# AT_short_bus.net
KiCad netlist of a schematic drawn in Altium Designer
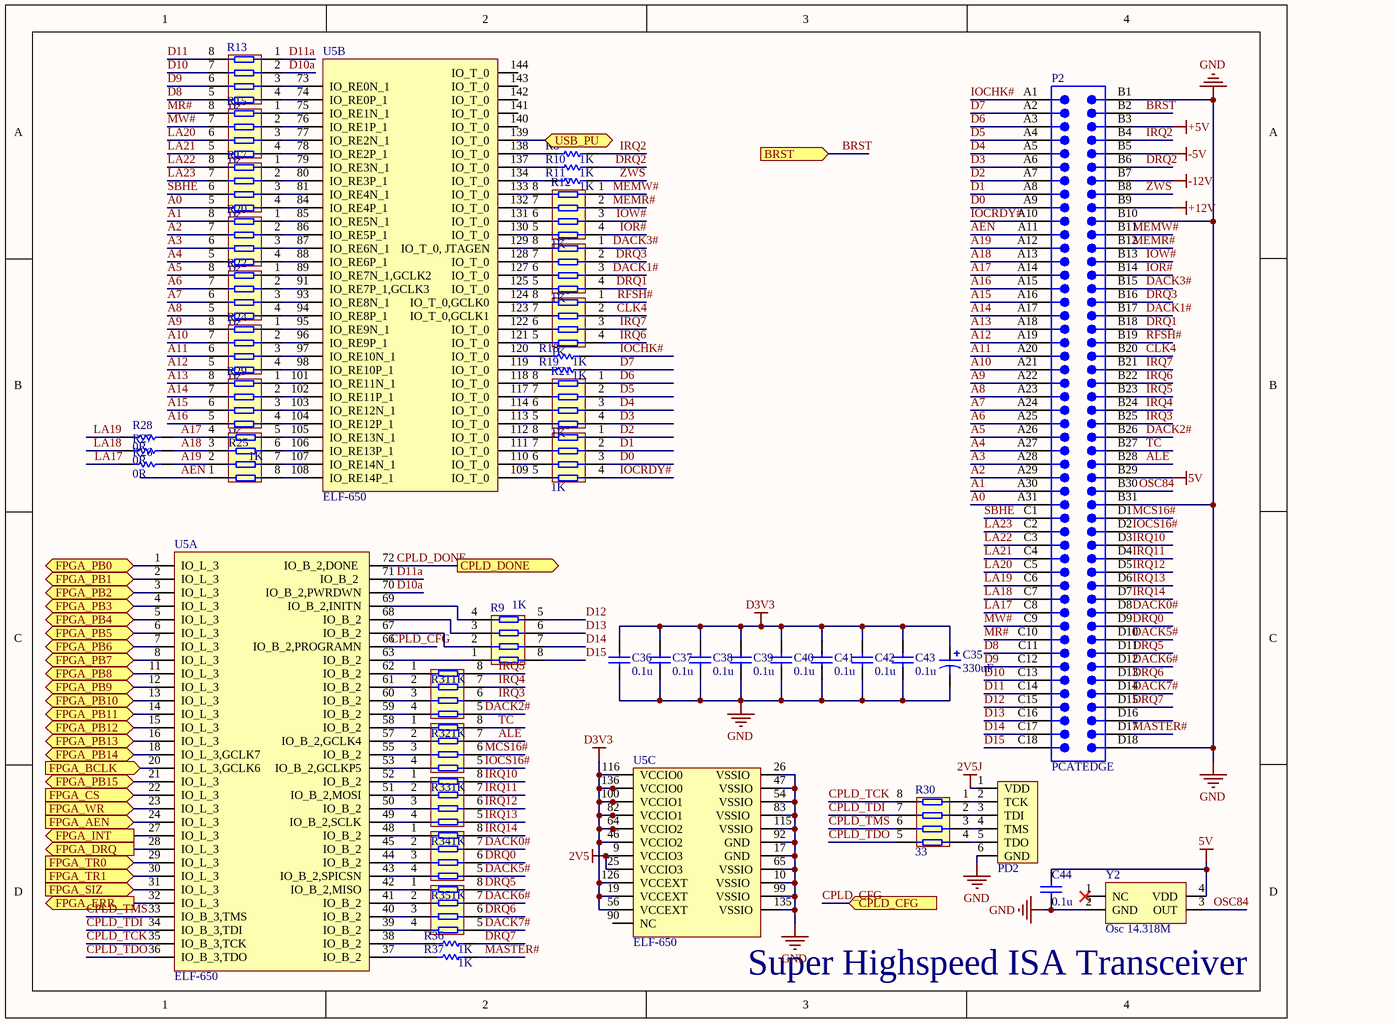
[diagram p0: AT short bus ( 7 x 4.2 inches).schdoc]

(export (version "E")
  (design (tool "Eeschema 10.0.6"))
  (components
    (comp (ref "C35")
      (value "330uF")
      (footprint "TanCap-1210")
      (description "Polarized Capacitor (Radial)")
      (fields (field (name "Comment") "330u") (field (name "PUBLISHER") "Altium Limited"))
      (libsource (lib "Miscellaneous Devices") (part "Cap Pol1"))
    )
    (comp (ref "C36")
      (value "0.1u")
      (footprint "0603C")
      (description "Capacitor")
      (fields (field (name "Comment") "Cap") (field (name "PUBLISHER") "Altium Limited"))
      (libsource (lib "Miscellaneous Devices") (part "Cap"))
    )
    (comp (ref "C37")
      (value "0.1u")
      (footprint "0603C")
      (description "Capacitor")
      (fields (field (name "Comment") "Cap") (field (name "PUBLISHER") "Altium Limited"))
      (libsource (lib "Miscellaneous Devices") (part "Cap"))
    )
    (comp (ref "C38")
      (value "0.1u")
      (footprint "0603C")
      (description "Capacitor")
      (fields (field (name "Comment") "Cap") (field (name "PUBLISHER") "Altium Limited"))
      (libsource (lib "Miscellaneous Devices") (part "Cap"))
    )
    (comp (ref "C39")
      (value "0.1u")
      (footprint "0603C")
      (description "Capacitor")
      (fields (field (name "Comment") "Cap") (field (name "PUBLISHER") "Altium Limited"))
      (libsource (lib "Miscellaneous Devices") (part "Cap"))
    )
    (comp (ref "C40")
      (value "0.1u")
      (footprint "0603C")
      (description "Capacitor")
      (fields (field (name "Comment") "Cap") (field (name "PUBLISHER") "Altium Limited"))
      (libsource (lib "Miscellaneous Devices") (part "Cap"))
    )
    (comp (ref "C41")
      (value "0.1u")
      (footprint "0603C")
      (description "Capacitor")
      (fields (field (name "Comment") "Cap") (field (name "PUBLISHER") "Altium Limited"))
      (libsource (lib "Miscellaneous Devices") (part "Cap"))
    )
    (comp (ref "C42")
      (value "0.1u")
      (footprint "0603C")
      (description "Capacitor")
      (fields (field (name "Comment") "Cap") (field (name "PUBLISHER") "Altium Limited"))
      (libsource (lib "Miscellaneous Devices") (part "Cap"))
    )
    (comp (ref "C43")
      (value "0.1u")
      (footprint "0603C")
      (description "Capacitor")
      (fields (field (name "Comment") "Cap") (field (name "PUBLISHER") "Altium Limited"))
      (libsource (lib "Miscellaneous Devices") (part "Cap"))
    )
    (comp (ref "C44")
      (value "0.1u")
      (footprint "0603C")
      (description "Capacitor")
      (fields (field (name "Comment") "Cap") (field (name "PUBLISHER") "Altium Limited"))
      (libsource (lib "Miscellaneous Devices") (part "Cap"))
    )
    (comp (ref "P2")
      (value "PCATEDGE")
      (footprint "PCATEDGE")
      (description "Card, 98-Position")
      (libsource (lib "*") (part "PCATEDGE"))
    )
    (comp (ref "PD2") (value "JTAG") (footprint "DBGP7") (libsource (lib "RV_AT_Ports") (part "JTAG")))
    (comp (ref "R8")
      (value "1K")
      (footprint "0603R")
      (description "Resistor")
      (fields (field (name "Comment") "Res1") (field (name "PUBLISHER") "Altium Limited"))
      (libsource (lib "Miscellaneous Devices") (part "Res1"))
    )
    (comp (ref "R9") (value "1K") (footprint "YC164") (libsource (lib "") (part "ResPak-8P4R_2")))
    (comp (ref "R10")
      (value "1K")
      (footprint "0603R")
      (description "Resistor")
      (fields (field (name "Comment") "Res1") (field (name "PUBLISHER") "Altium Limited"))
      (libsource (lib "Miscellaneous Devices") (part "Res1"))
    )
    (comp (ref "R11")
      (value "1K")
      (footprint "0603R")
      (description "Resistor")
      (fields (field (name "Comment") "Res1") (field (name "PUBLISHER") "Altium Limited"))
      (libsource (lib "Miscellaneous Devices") (part "Res1"))
    )
    (comp (ref "R12") (value "1K") (footprint "YC164") (libsource (lib "PublicSch") (part "ResPak-8P4R")))
    (comp (ref "R13") (value "1K") (footprint "YC164") (libsource (lib "PublicSch") (part "ResPak-8P4R")))
    (comp (ref "R14") (value "1K") (footprint "YC164") (libsource (lib "PublicSch") (part "ResPak-8P4R")))
    (comp (ref "R15") (value "1K") (footprint "YC164") (libsource (lib "PublicSch") (part "ResPak-8P4R")))
    (comp (ref "R16") (value "1K") (footprint "YC164") (libsource (lib "PublicSch") (part "ResPak-8P4R")))
    (comp (ref "R17") (value "1K") (footprint "YC164") (libsource (lib "PublicSch") (part "ResPak-8P4R")))
    (comp (ref "R18")
      (value "1K")
      (footprint "0603R")
      (description "Resistor")
      (fields (field (name "Comment") "Res1") (field (name "PUBLISHER") "Altium Limited"))
      (libsource (lib "Miscellaneous Devices") (part "Res1"))
    )
    (comp (ref "R19")
      (value "1K")
      (footprint "0603R")
      (description "Resistor")
      (fields (field (name "Comment") "Res1") (field (name "PUBLISHER") "Altium Limited"))
      (libsource (lib "Miscellaneous Devices") (part "Res1"))
    )
    (comp (ref "R20") (value "1K") (footprint "YC164") (libsource (lib "PublicSch") (part "ResPak-8P4R")))
    (comp (ref "R21") (value "1K") (footprint "YC164") (libsource (lib "PublicSch") (part "ResPak-8P4R")))
    (comp (ref "R22") (value "1K") (footprint "YC164") (libsource (lib "PublicSch") (part "ResPak-8P4R")))
    (comp (ref "R23") (value "1K") (footprint "YC164") (libsource (lib "PublicSch") (part "ResPak-8P4R")))
    (comp (ref "R24") (value "1K") (footprint "YC164") (libsource (lib "PublicSch") (part "ResPak-8P4R")))
    (comp (ref "R25") (value "1K") (footprint "YC164") (libsource (lib "") (part "ResPak-8P4R_2")))
    (comp (ref "R26")
      (value "0R")
      (footprint "0603R")
      (description "Resistor")
      (fields (field (name "Comment") "Res1") (field (name "PUBLISHER") "Altium Limited"))
      (libsource (lib "Miscellaneous Devices") (part "Res1"))
    )
    (comp (ref "R27")
      (value "0R")
      (footprint "0603R")
      (description "Resistor")
      (fields (field (name "Comment") "Res1") (field (name "PUBLISHER") "Altium Limited"))
      (libsource (lib "Miscellaneous Devices") (part "Res1"))
    )
    (comp (ref "R28")
      (value "0R")
      (footprint "0603R")
      (description "Resistor")
      (fields (field (name "Comment") "Res1") (field (name "PUBLISHER") "Altium Limited"))
      (libsource (lib "Miscellaneous Devices") (part "Res1"))
    )
    (comp (ref "R29") (value "1K") (footprint "YC164") (libsource (lib "PublicSch") (part "ResPak-8P4R")))
    (comp (ref "R30") (value "33") (footprint "YC164") (libsource (lib "PublicSch") (part "ResPak-8P4R")))
    (comp (ref "R31") (value "1K") (footprint "YC164") (libsource (lib "") (part "ResPak-8P4R_1")))
    (comp (ref "R32") (value "1K") (footprint "YC164") (libsource (lib "") (part "ResPak-8P4R_1")))
    (comp (ref "R33") (value "1K") (footprint "YC164") (libsource (lib "") (part "ResPak-8P4R_1")))
    (comp (ref "R34") (value "1K") (footprint "YC164") (libsource (lib "") (part "ResPak-8P4R_1")))
    (comp (ref "R35") (value "1K") (footprint "YC164") (libsource (lib "") (part "ResPak-8P4R_1")))
    (comp (ref "R36")
      (value "1K")
      (footprint "0603R")
      (description "Resistor")
      (fields (field (name "Comment") "Res1") (field (name "PUBLISHER") "Altium Limited"))
      (libsource (lib "Miscellaneous Devices") (part "Res1"))
    )
    (comp (ref "R37")
      (value "1K")
      (footprint "0603R")
      (description "Resistor")
      (fields (field (name "Comment") "Res1") (field (name "PUBLISHER") "Altium Limited"))
      (libsource (lib "Miscellaneous Devices") (part "Res1"))
    )
    (comp (ref "U5")
      (value "ELF-650")
      (footprint "LQFP144-1")
      (description "GP CPLD")
      (libsource (lib "AnLogic_FPGAs") (part "EF1A650LQ144"))
    )
    (comp (ref "Y2") (value "Osc 14.318M") (footprint "XTAL-3225") (libsource (lib "74xLogic") (part "OSC")))
  )
  (nets
    (net (code "1") (name "+5V") (class "Default")
      (node (ref "P2") (pin "B3") (pinfunction "B3_B3") (pintype "passive"))
    )
    (net (code "2") (name "+12V") (class "Default")
      (node (ref "P2") (pin "B9") (pinfunction "B9_B9") (pintype "passive"))
    )
    (net (code "3") (name "-5V") (class "Default")
      (node (ref "P2") (pin "B5") (pinfunction "B5_B5") (pintype "passive"))
    )
    (net (code "4") (name "-12V") (class "Default")
      (node (ref "P2") (pin "B7") (pinfunction "B7_B7") (pintype "passive"))
    )
    (net (code "5") (name "/A0") (class "Default")
      (node (ref "P2") (pin "A31") (pinfunction "A31_A31") (pintype "passive"))
      (node (ref "R17") (pin "5") (pinfunction "5_5") (pintype "passive"))
    )
    (net (code "6") (name "/A1") (class "Default")
      (node (ref "P2") (pin "A30") (pinfunction "A30_A30") (pintype "passive"))
      (node (ref "R20") (pin "8") (pinfunction "8_8") (pintype "passive"))
    )
    (net (code "7") (name "/A2") (class "Default")
      (node (ref "P2") (pin "A29") (pinfunction "A29_A29") (pintype "passive"))
      (node (ref "R20") (pin "7") (pinfunction "7_7") (pintype "passive"))
    )
    (net (code "8") (name "/A3") (class "Default")
      (node (ref "P2") (pin "A28") (pinfunction "A28_A28") (pintype "passive"))
      (node (ref "R20") (pin "6") (pinfunction "6_6") (pintype "passive"))
    )
    (net (code "9") (name "/A4") (class "Default")
      (node (ref "P2") (pin "A27") (pinfunction "A27_A27") (pintype "passive"))
      (node (ref "R20") (pin "5") (pinfunction "5_5") (pintype "passive"))
    )
    (net (code "10") (name "/A5") (class "Default")
      (node (ref "P2") (pin "A26") (pinfunction "A26_A26") (pintype "passive"))
      (node (ref "R22") (pin "8") (pinfunction "8_8") (pintype "passive"))
    )
    (net (code "11") (name "/A6") (class "Default")
      (node (ref "P2") (pin "A25") (pinfunction "A25_A25") (pintype "passive"))
      (node (ref "R22") (pin "7") (pinfunction "7_7") (pintype "passive"))
    )
    (net (code "12") (name "/A7") (class "Default")
      (node (ref "P2") (pin "A24") (pinfunction "A24_A24") (pintype "passive"))
      (node (ref "R22") (pin "6") (pinfunction "6_6") (pintype "passive"))
    )
    (net (code "13") (name "/A8") (class "Default")
      (node (ref "P2") (pin "A23") (pinfunction "A23_A23") (pintype "passive"))
      (node (ref "R22") (pin "5") (pinfunction "5_5") (pintype "passive"))
    )
    (net (code "14") (name "/A9") (class "Default")
      (node (ref "P2") (pin "A22") (pinfunction "A22_A22") (pintype "passive"))
      (node (ref "R24") (pin "8") (pinfunction "8_8") (pintype "passive"))
    )
    (net (code "15") (name "/A10") (class "Default")
      (node (ref "P2") (pin "A21") (pinfunction "A21_A21") (pintype "passive"))
      (node (ref "R24") (pin "7") (pinfunction "7_7") (pintype "passive"))
    )
    (net (code "16") (name "/A11") (class "Default")
      (node (ref "P2") (pin "A20") (pinfunction "A20_A20") (pintype "passive"))
      (node (ref "R24") (pin "6") (pinfunction "6_6") (pintype "passive"))
    )
    (net (code "17") (name "/A12") (class "Default")
      (node (ref "P2") (pin "A19") (pinfunction "A19_A19") (pintype "passive"))
      (node (ref "R24") (pin "5") (pinfunction "5_5") (pintype "passive"))
    )
    (net (code "18") (name "/A13") (class "Default")
      (node (ref "P2") (pin "A18") (pinfunction "A18_A18") (pintype "passive"))
      (node (ref "R29") (pin "8") (pinfunction "8_8") (pintype "passive"))
    )
    (net (code "19") (name "/A14") (class "Default")
      (node (ref "P2") (pin "A17") (pinfunction "A17_A17") (pintype "passive"))
      (node (ref "R29") (pin "7") (pinfunction "7_7") (pintype "passive"))
    )
    (net (code "20") (name "/A15") (class "Default")
      (node (ref "P2") (pin "A16") (pinfunction "A16_A16") (pintype "passive"))
      (node (ref "R29") (pin "6") (pinfunction "6_6") (pintype "passive"))
    )
    (net (code "21") (name "/A16") (class "Default")
      (node (ref "P2") (pin "A15") (pinfunction "A15_A15") (pintype "passive"))
      (node (ref "R29") (pin "5") (pinfunction "5_5") (pintype "passive"))
    )
    (net (code "22") (name "/A17") (class "Default")
      (node (ref "P2") (pin "A14") (pinfunction "A14_A14") (pintype "passive"))
      (node (ref "R25") (pin "4") (pinfunction "4_4") (pintype "passive"))
      (node (ref "R28") (pin "2") (pinfunction "2_2") (pintype "passive"))
    )
    (net (code "23") (name "/A18") (class "Default")
      (node (ref "P2") (pin "A13") (pinfunction "A13_A13") (pintype "passive"))
      (node (ref "R25") (pin "3") (pinfunction "3_3") (pintype "passive"))
      (node (ref "R27") (pin "2") (pinfunction "2_2") (pintype "passive"))
    )
    (net (code "24") (name "/A19") (class "Default")
      (node (ref "P2") (pin "A12") (pinfunction "A12_A12") (pintype "passive"))
      (node (ref "R25") (pin "2") (pinfunction "2_2") (pintype "passive"))
      (node (ref "R26") (pin "2") (pinfunction "2_2") (pintype "passive"))
    )
    (net (code "25") (name "/AEN") (class "Default")
      (node (ref "P2") (pin "A11") (pinfunction "A11_A11") (pintype "passive"))
      (node (ref "R25") (pin "1") (pinfunction "1_1") (pintype "passive"))
    )
    (net (code "26") (name "/ALE") (class "Default")
      (node (ref "P2") (pin "B28") (pinfunction "B28_B28") (pintype "passive"))
      (node (ref "R32") (pin "7") (pinfunction "7_7") (pintype "passive"))
    )
    (net (code "27") (name "/BRST") (class "Default")
      (node (ref "P2") (pin "B2") (pinfunction "B2_B2") (pintype "passive"))
    )
    (net (code "28") (name "/CLK4") (class "Default")
      (node (ref "P2") (pin "B20") (pinfunction "B20_B20") (pintype "passive"))
      (node (ref "R16") (pin "2") (pinfunction "2_2") (pintype "passive"))
    )
    (net (code "29") (name "/CPLD_CFG") (class "Default")
      (node (ref "U5") (pin "66") (pinfunction "IO_B_2,PROGRAMN_66") (pintype "passive"))
    )
    (net (code "30") (name "/CPLD_DONE") (class "Default")
      (node (ref "U5") (pin "72") (pinfunction "IO_B_2,DONE_72") (pintype "passive"))
    )
    (net (code "31") (name "/CPLD_TCK") (class "Default")
      (node (ref "R30") (pin "8") (pinfunction "8_8") (pintype "passive"))
      (node (ref "U5") (pin "35") (pinfunction "IO_B_3,TCK_35") (pintype "passive"))
    )
    (net (code "32") (name "/CPLD_TDI") (class "Default")
      (node (ref "R30") (pin "7") (pinfunction "7_7") (pintype "passive"))
      (node (ref "U5") (pin "34") (pinfunction "IO_B_3,TDI_34") (pintype "passive"))
    )
    (net (code "33") (name "/CPLD_TDO") (class "Default")
      (node (ref "R30") (pin "5") (pinfunction "5_5") (pintype "passive"))
      (node (ref "U5") (pin "36") (pinfunction "IO_B_3,TDO_36") (pintype "passive"))
    )
    (net (code "34") (name "/CPLD_TMS") (class "Default")
      (node (ref "R30") (pin "6") (pinfunction "6_6") (pintype "passive"))
      (node (ref "U5") (pin "33") (pinfunction "IO_B_3,TMS_33") (pintype "passive"))
    )
    (net (code "35") (name "/D0") (class "Default")
      (node (ref "P2") (pin "A9") (pinfunction "A9_A9") (pintype "passive"))
      (node (ref "R23") (pin "3") (pinfunction "3_3") (pintype "passive"))
    )
    (net (code "36") (name "/D1") (class "Default")
      (node (ref "P2") (pin "A8") (pinfunction "A8_A8") (pintype "passive"))
      (node (ref "R23") (pin "2") (pinfunction "2_2") (pintype "passive"))
    )
    (net (code "37") (name "/D2") (class "Default")
      (node (ref "P2") (pin "A7") (pinfunction "A7_A7") (pintype "passive"))
      (node (ref "R23") (pin "1") (pinfunction "1_1") (pintype "passive"))
    )
    (net (code "38") (name "/D3") (class "Default")
      (node (ref "P2") (pin "A6") (pinfunction "A6_A6") (pintype "passive"))
      (node (ref "R21") (pin "4") (pinfunction "4_4") (pintype "passive"))
    )
    (net (code "39") (name "/D4") (class "Default")
      (node (ref "P2") (pin "A5") (pinfunction "A5_A5") (pintype "passive"))
      (node (ref "R21") (pin "3") (pinfunction "3_3") (pintype "passive"))
    )
    (net (code "40") (name "/D5") (class "Default")
      (node (ref "P2") (pin "A4") (pinfunction "A4_A4") (pintype "passive"))
      (node (ref "R21") (pin "2") (pinfunction "2_2") (pintype "passive"))
    )
    (net (code "41") (name "/D6") (class "Default")
      (node (ref "P2") (pin "A3") (pinfunction "A3_A3") (pintype "passive"))
      (node (ref "R21") (pin "1") (pinfunction "1_1") (pintype "passive"))
    )
    (net (code "42") (name "/D7") (class "Default")
      (node (ref "P2") (pin "A2") (pinfunction "A2_A2") (pintype "passive"))
      (node (ref "R19") (pin "1") (pinfunction "1_1") (pintype "passive"))
    )
    (net (code "43") (name "/D8") (class "Default")
      (node (ref "P2") (pin "C11") (pinfunction "C11_C11") (pintype "passive"))
      (node (ref "R13") (pin "5") (pinfunction "5_5") (pintype "passive"))
    )
    (net (code "44") (name "/D9") (class "Default")
      (node (ref "P2") (pin "C12") (pinfunction "C12_C12") (pintype "passive"))
      (node (ref "R13") (pin "6") (pinfunction "6_6") (pintype "passive"))
    )
    (net (code "45") (name "/D10") (class "Default")
      (node (ref "P2") (pin "C13") (pinfunction "C13_C13") (pintype "passive"))
      (node (ref "R13") (pin "7") (pinfunction "7_7") (pintype "passive"))
    )
    (net (code "46") (name "/D10a") (class "Default")
      (node (ref "R13") (pin "2") (pinfunction "2_2") (pintype "passive"))
      (node (ref "U5") (pin "70") (pinfunction "IO_B_2,PWRDWN_70") (pintype "passive"))
    )
    (net (code "47") (name "/D11") (class "Default")
      (node (ref "P2") (pin "C14") (pinfunction "C14_C14") (pintype "passive"))
      (node (ref "R13") (pin "8") (pinfunction "8_8") (pintype "passive"))
    )
    (net (code "48") (name "/D11a") (class "Default")
      (node (ref "R13") (pin "1") (pinfunction "1_1") (pintype "passive"))
      (node (ref "U5") (pin "71") (pinfunction "IO_B_2_71") (pintype "passive"))
    )
    (net (code "49") (name "/D12") (class "Default")
      (node (ref "P2") (pin "C15") (pinfunction "C15_C15") (pintype "passive"))
      (node (ref "R9") (pin "5") (pinfunction "5_5") (pintype "passive"))
    )
    (net (code "50") (name "/D13") (class "Default")
      (node (ref "P2") (pin "C16") (pinfunction "C16_C16") (pintype "passive"))
      (node (ref "R9") (pin "6") (pinfunction "6_6") (pintype "passive"))
    )
    (net (code "51") (name "/D14") (class "Default")
      (node (ref "P2") (pin "C17") (pinfunction "C17_C17") (pintype "passive"))
      (node (ref "R9") (pin "7") (pinfunction "7_7") (pintype "passive"))
    )
    (net (code "52") (name "/D15") (class "Default")
      (node (ref "P2") (pin "C18") (pinfunction "C18_C18") (pintype "passive"))
      (node (ref "R9") (pin "8") (pinfunction "8_8") (pintype "passive"))
    )
    (net (code "53") (name "/DACK0#") (class "Default")
      (node (ref "P2") (pin "D8") (pinfunction "D8_D8") (pintype "passive"))
      (node (ref "R34") (pin "7") (pinfunction "7_7") (pintype "passive"))
    )
    (net (code "54") (name "/DACK1#") (class "Default")
      (node (ref "P2") (pin "B17") (pinfunction "B17_B17") (pintype "passive"))
      (node (ref "R14") (pin "3") (pinfunction "3_3") (pintype "passive"))
    )
    (net (code "55") (name "/DACK2#") (class "Default")
      (node (ref "P2") (pin "B26") (pinfunction "B26_B26") (pintype "passive"))
      (node (ref "R31") (pin "5") (pinfunction "5_5") (pintype "passive"))
    )
    (net (code "56") (name "/DACK3#") (class "Default")
      (node (ref "P2") (pin "B15") (pinfunction "B15_B15") (pintype "passive"))
      (node (ref "R14") (pin "1") (pinfunction "1_1") (pintype "passive"))
    )
    (net (code "57") (name "/DACK5#") (class "Default")
      (node (ref "P2") (pin "D10") (pinfunction "D10_D10") (pintype "passive"))
      (node (ref "R34") (pin "5") (pinfunction "5_5") (pintype "passive"))
    )
    (net (code "58") (name "/DACK6#") (class "Default")
      (node (ref "P2") (pin "D12") (pinfunction "D12_D12") (pintype "passive"))
      (node (ref "R35") (pin "7") (pinfunction "7_7") (pintype "passive"))
    )
    (net (code "59") (name "/DACK7#") (class "Default")
      (node (ref "P2") (pin "D14") (pinfunction "D14_D14") (pintype "passive"))
      (node (ref "R35") (pin "5") (pinfunction "5_5") (pintype "passive"))
    )
    (net (code "60") (name "/DRQ0") (class "Default")
      (node (ref "P2") (pin "D9") (pinfunction "D9_D9") (pintype "passive"))
      (node (ref "R34") (pin "6") (pinfunction "6_6") (pintype "passive"))
    )
    (net (code "61") (name "/DRQ1") (class "Default")
      (node (ref "P2") (pin "B18") (pinfunction "B18_B18") (pintype "passive"))
      (node (ref "R14") (pin "4") (pinfunction "4_4") (pintype "passive"))
    )
    (net (code "62") (name "/DRQ2") (class "Default")
      (node (ref "P2") (pin "B6") (pinfunction "B6_B6") (pintype "passive"))
      (node (ref "R10") (pin "1") (pinfunction "1_1") (pintype "passive"))
    )
    (net (code "63") (name "/DRQ3") (class "Default")
      (node (ref "P2") (pin "B16") (pinfunction "B16_B16") (pintype "passive"))
      (node (ref "R14") (pin "2") (pinfunction "2_2") (pintype "passive"))
    )
    (net (code "64") (name "/DRQ5") (class "Default")
      (node (ref "P2") (pin "D11") (pinfunction "D11_D11") (pintype "passive"))
      (node (ref "R35") (pin "8") (pinfunction "8_8") (pintype "passive"))
    )
    (net (code "65") (name "/DRQ6") (class "Default")
      (node (ref "P2") (pin "D13") (pinfunction "D13_D13") (pintype "passive"))
      (node (ref "R35") (pin "6") (pinfunction "6_6") (pintype "passive"))
    )
    (net (code "66") (name "/DRQ7") (class "Default")
      (node (ref "P2") (pin "D15") (pinfunction "D15_D15") (pintype "passive"))
      (node (ref "R36") (pin "1") (pinfunction "1_1") (pintype "passive"))
    )
    (net (code "67") (name "/FPGA_AEN") (class "Default")
      (node (ref "U5") (pin "24") (pinfunction "IO_L_3_24") (pintype "passive"))
    )
    (net (code "68") (name "/FPGA_BCLK") (class "Default")
      (node (ref "U5") (pin "20") (pinfunction "IO_L_3,GCLK6_20") (pintype "passive"))
    )
    (net (code "69") (name "/FPGA_CS") (class "Default")
      (node (ref "U5") (pin "22") (pinfunction "IO_L_3_22") (pintype "passive"))
    )
    (net (code "70") (name "/FPGA_DRQ") (class "Default")
      (node (ref "U5") (pin "28") (pinfunction "IO_L_3_28") (pintype "passive"))
    )
    (net (code "71") (name "/FPGA_ERR") (class "Default")
      (node (ref "U5") (pin "32") (pinfunction "IO_L_3_32") (pintype "passive"))
    )
    (net (code "72") (name "/FPGA_INT") (class "Default")
      (node (ref "U5") (pin "27") (pinfunction "IO_L_3_27") (pintype "passive"))
    )
    (net (code "73") (name "/FPGA_PB0") (class "Default")
      (node (ref "U5") (pin "1") (pinfunction "IO_L_3_1") (pintype "passive"))
    )
    (net (code "74") (name "/FPGA_PB1") (class "Default")
      (node (ref "U5") (pin "2") (pinfunction "IO_L_3_2") (pintype "passive"))
    )
    (net (code "75") (name "/FPGA_PB2") (class "Default")
      (node (ref "U5") (pin "3") (pinfunction "IO_L_3_3") (pintype "passive"))
    )
    (net (code "76") (name "/FPGA_PB3") (class "Default")
      (node (ref "U5") (pin "4") (pinfunction "IO_L_3_4") (pintype "passive"))
    )
    (net (code "77") (name "/FPGA_PB4") (class "Default")
      (node (ref "U5") (pin "5") (pinfunction "IO_L_3_5") (pintype "passive"))
    )
    (net (code "78") (name "/FPGA_PB5") (class "Default")
      (node (ref "U5") (pin "6") (pinfunction "IO_L_3_6") (pintype "passive"))
    )
    (net (code "79") (name "/FPGA_PB6") (class "Default")
      (node (ref "U5") (pin "7") (pinfunction "IO_L_3_7") (pintype "passive"))
    )
    (net (code "80") (name "/FPGA_PB7") (class "Default")
      (node (ref "U5") (pin "8") (pinfunction "IO_L_3_8") (pintype "passive"))
    )
    (net (code "81") (name "/FPGA_PB8") (class "Default")
      (node (ref "U5") (pin "11") (pinfunction "IO_L_3_11") (pintype "passive"))
    )
    (net (code "82") (name "/FPGA_PB9") (class "Default")
      (node (ref "U5") (pin "12") (pinfunction "IO_L_3_12") (pintype "passive"))
    )
    (net (code "83") (name "/FPGA_PB10") (class "Default")
      (node (ref "U5") (pin "13") (pinfunction "IO_L_3_13") (pintype "passive"))
    )
    (net (code "84") (name "/FPGA_PB11") (class "Default")
      (node (ref "U5") (pin "14") (pinfunction "IO_L_3_14") (pintype "passive"))
    )
    (net (code "85") (name "/FPGA_PB12") (class "Default")
      (node (ref "U5") (pin "15") (pinfunction "IO_L_3_15") (pintype "passive"))
    )
    (net (code "86") (name "/FPGA_PB13") (class "Default")
      (node (ref "U5") (pin "16") (pinfunction "IO_L_3_16") (pintype "passive"))
    )
    (net (code "87") (name "/FPGA_PB14") (class "Default")
      (node (ref "U5") (pin "18") (pinfunction "IO_L_3,GCLK7_18") (pintype "passive"))
    )
    (net (code "88") (name "/FPGA_PB15") (class "Default")
      (node (ref "U5") (pin "21") (pinfunction "IO_L_3_21") (pintype "passive"))
    )
    (net (code "89") (name "/FPGA_SIZ") (class "Default")
      (node (ref "U5") (pin "31") (pinfunction "IO_L_3_31") (pintype "passive"))
    )
    (net (code "90") (name "/FPGA_TR0") (class "Default")
      (node (ref "U5") (pin "29") (pinfunction "IO_L_3_29") (pintype "passive"))
    )
    (net (code "91") (name "/FPGA_TR1") (class "Default")
      (node (ref "U5") (pin "30") (pinfunction "IO_L_3_30") (pintype "passive"))
    )
    (net (code "92") (name "/FPGA_WR") (class "Default")
      (node (ref "U5") (pin "23") (pinfunction "IO_L_3_23") (pintype "passive"))
    )
    (net (code "93") (name "/IOCHK#") (class "Default")
      (node (ref "P2") (pin "A1") (pinfunction "A1_A1") (pintype "passive"))
      (node (ref "R18") (pin "1") (pinfunction "1_1") (pintype "passive"))
    )
    (net (code "94") (name "/IOCRDY#") (class "Default")
      (node (ref "P2") (pin "A10") (pinfunction "A10_A10") (pintype "passive"))
      (node (ref "R23") (pin "4") (pinfunction "4_4") (pintype "passive"))
    )
    (net (code "95") (name "/IOCS16#") (class "Default")
      (node (ref "P2") (pin "D2") (pinfunction "D2_D2") (pintype "passive"))
      (node (ref "R32") (pin "5") (pinfunction "5_5") (pintype "passive"))
    )
    (net (code "96") (name "/IOR#") (class "Default")
      (node (ref "P2") (pin "B14") (pinfunction "B14_B14") (pintype "passive"))
      (node (ref "R12") (pin "4") (pinfunction "4_4") (pintype "passive"))
    )
    (net (code "97") (name "/IOW#") (class "Default")
      (node (ref "P2") (pin "B13") (pinfunction "B13_B13") (pintype "passive"))
      (node (ref "R12") (pin "3") (pinfunction "3_3") (pintype "passive"))
    )
    (net (code "98") (name "/IRQ2") (class "Default")
      (node (ref "P2") (pin "B4") (pinfunction "B4_B4") (pintype "passive"))
      (node (ref "R8") (pin "1") (pinfunction "1_1") (pintype "passive"))
    )
    (net (code "99") (name "/IRQ3") (class "Default")
      (node (ref "P2") (pin "B25") (pinfunction "B25_B25") (pintype "passive"))
      (node (ref "R31") (pin "6") (pinfunction "6_6") (pintype "passive"))
    )
    (net (code "100") (name "/IRQ4") (class "Default")
      (node (ref "P2") (pin "B24") (pinfunction "B24_B24") (pintype "passive"))
      (node (ref "R31") (pin "7") (pinfunction "7_7") (pintype "passive"))
    )
    (net (code "101") (name "/IRQ5") (class "Default")
      (node (ref "P2") (pin "B23") (pinfunction "B23_B23") (pintype "passive"))
      (node (ref "R31") (pin "8") (pinfunction "8_8") (pintype "passive"))
    )
    (net (code "102") (name "/IRQ6") (class "Default")
      (node (ref "P2") (pin "B22") (pinfunction "B22_B22") (pintype "passive"))
      (node (ref "R16") (pin "4") (pinfunction "4_4") (pintype "passive"))
    )
    (net (code "103") (name "/IRQ7") (class "Default")
      (node (ref "P2") (pin "B21") (pinfunction "B21_B21") (pintype "passive"))
      (node (ref "R16") (pin "3") (pinfunction "3_3") (pintype "passive"))
    )
    (net (code "104") (name "/IRQ10") (class "Default")
      (node (ref "P2") (pin "D3") (pinfunction "D3_D3") (pintype "passive"))
      (node (ref "R33") (pin "8") (pinfunction "8_8") (pintype "passive"))
    )
    (net (code "105") (name "/IRQ11") (class "Default")
      (node (ref "P2") (pin "D4") (pinfunction "D4_D4") (pintype "passive"))
      (node (ref "R33") (pin "7") (pinfunction "7_7") (pintype "passive"))
    )
    (net (code "106") (name "/IRQ12") (class "Default")
      (node (ref "P2") (pin "D5") (pinfunction "D5_D5") (pintype "passive"))
      (node (ref "R33") (pin "6") (pinfunction "6_6") (pintype "passive"))
    )
    (net (code "107") (name "/IRQ13") (class "Default")
      (node (ref "P2") (pin "D6") (pinfunction "D6_D6") (pintype "passive"))
      (node (ref "R33") (pin "5") (pinfunction "5_5") (pintype "passive"))
    )
    (net (code "108") (name "/IRQ14") (class "Default")
      (node (ref "P2") (pin "D7") (pinfunction "D7_D7") (pintype "passive"))
      (node (ref "R34") (pin "8") (pinfunction "8_8") (pintype "passive"))
    )
    (net (code "109") (name "/LA17") (class "Default")
      (node (ref "P2") (pin "C8") (pinfunction "C8_C8") (pintype "passive"))
      (node (ref "R26") (pin "1") (pinfunction "1_1") (pintype "passive"))
    )
    (net (code "110") (name "/LA18") (class "Default")
      (node (ref "P2") (pin "C7") (pinfunction "C7_C7") (pintype "passive"))
      (node (ref "R27") (pin "1") (pinfunction "1_1") (pintype "passive"))
    )
    (net (code "111") (name "/LA19") (class "Default")
      (node (ref "P2") (pin "C6") (pinfunction "C6_C6") (pintype "passive"))
      (node (ref "R28") (pin "1") (pinfunction "1_1") (pintype "passive"))
    )
    (net (code "112") (name "/LA20") (class "Default")
      (node (ref "P2") (pin "C5") (pinfunction "C5_C5") (pintype "passive"))
      (node (ref "R15") (pin "6") (pinfunction "6_6") (pintype "passive"))
    )
    (net (code "113") (name "/LA21") (class "Default")
      (node (ref "P2") (pin "C4") (pinfunction "C4_C4") (pintype "passive"))
      (node (ref "R15") (pin "5") (pinfunction "5_5") (pintype "passive"))
    )
    (net (code "114") (name "/LA22") (class "Default")
      (node (ref "P2") (pin "C3") (pinfunction "C3_C3") (pintype "passive"))
      (node (ref "R17") (pin "8") (pinfunction "8_8") (pintype "passive"))
    )
    (net (code "115") (name "/LA23") (class "Default")
      (node (ref "P2") (pin "C2") (pinfunction "C2_C2") (pintype "passive"))
      (node (ref "R17") (pin "7") (pinfunction "7_7") (pintype "passive"))
    )
    (net (code "116") (name "/MASTER#") (class "Default")
      (node (ref "P2") (pin "D17") (pinfunction "D17_D17") (pintype "passive"))
      (node (ref "R37") (pin "1") (pinfunction "1_1") (pintype "passive"))
    )
    (net (code "117") (name "/MCS16#") (class "Default")
      (node (ref "P2") (pin "D1") (pinfunction "D1_D1") (pintype "passive"))
      (node (ref "R32") (pin "6") (pinfunction "6_6") (pintype "passive"))
    )
    (net (code "118") (name "/MEMR#") (class "Default")
      (node (ref "P2") (pin "B12") (pinfunction "B12_B12") (pintype "passive"))
      (node (ref "R12") (pin "2") (pinfunction "2_2") (pintype "passive"))
    )
    (net (code "119") (name "/MEMW#") (class "Default")
      (node (ref "P2") (pin "B11") (pinfunction "B11_B11") (pintype "passive"))
      (node (ref "R12") (pin "1") (pinfunction "1_1") (pintype "passive"))
    )
    (net (code "120") (name "/MR#") (class "Default")
      (node (ref "P2") (pin "C10") (pinfunction "C10_C10") (pintype "passive"))
      (node (ref "R15") (pin "8") (pinfunction "8_8") (pintype "passive"))
    )
    (net (code "121") (name "/MW#") (class "Default")
      (node (ref "P2") (pin "C9") (pinfunction "C9_C9") (pintype "passive"))
      (node (ref "R15") (pin "7") (pinfunction "7_7") (pintype "passive"))
    )
    (net (code "122") (name "/OSC84") (class "Default")
      (node (ref "P2") (pin "B30") (pinfunction "B30_B30") (pintype "passive"))
      (node (ref "Y2") (pin "3") (pinfunction "OUT_3") (pintype "passive"))
    )
    (net (code "123") (name "/RFSH#") (class "Default")
      (node (ref "P2") (pin "B19") (pinfunction "B19_B19") (pintype "passive"))
      (node (ref "R16") (pin "1") (pinfunction "1_1") (pintype "passive"))
    )
    (net (code "124") (name "/SBHE") (class "Default")
      (node (ref "P2") (pin "C1") (pinfunction "C1_C1") (pintype "passive"))
      (node (ref "R17") (pin "6") (pinfunction "6_6") (pintype "passive"))
    )
    (net (code "125") (name "/TC") (class "Default")
      (node (ref "P2") (pin "B27") (pinfunction "B27_B27") (pintype "passive"))
      (node (ref "R32") (pin "8") (pinfunction "8_8") (pintype "passive"))
    )
    (net (code "126") (name "/USB_PU") (class "Default")
      (node (ref "U5") (pin "139") (pinfunction "IO_T_0_139") (pintype "passive"))
    )
    (net (code "127") (name "/ZWS") (class "Default")
      (node (ref "P2") (pin "B8") (pinfunction "B8_B8") (pintype "passive"))
      (node (ref "R11") (pin "1") (pinfunction "1_1") (pintype "passive"))
    )
    (net (code "128") (name "2V5") (class "Default")
      (node (ref "U5") (pin "25") (pinfunction "VCCIO3_25") (pintype "passive"))
      (node (ref "U5") (pin "9") (pinfunction "VCCIO3_9") (pintype "passive"))
    )
    (net (code "129") (name "2V5J") (class "Default")
      (node (ref "PD2") (pin "1") (pinfunction "VDD_1") (pintype "passive"))
    )
    (net (code "130") (name "5V") (class "Default")
      (node (ref "C44") (pin "2") (pinfunction "2_2") (pintype "passive"))
      (node (ref "P2") (pin "B29") (pinfunction "B29_B29") (pintype "passive"))
      (node (ref "Y2") (pin "4") (pinfunction "VDD_4") (pintype "passive"))
    )
    (net (code "131") (name "D3V3") (class "Default")
      (node (ref "C35") (pin "1") (pinfunction "1_1") (pintype "passive"))
      (node (ref "C36") (pin "1") (pinfunction "1_1") (pintype "passive"))
      (node (ref "C37") (pin "1") (pinfunction "1_1") (pintype "passive"))
      (node (ref "C38") (pin "1") (pinfunction "1_1") (pintype "passive"))
      (node (ref "C39") (pin "1") (pinfunction "1_1") (pintype "passive"))
      (node (ref "C40") (pin "1") (pinfunction "1_1") (pintype "passive"))
      (node (ref "C41") (pin "1") (pinfunction "1_1") (pintype "passive"))
      (node (ref "C42") (pin "1") (pinfunction "1_1") (pintype "passive"))
      (node (ref "C43") (pin "1") (pinfunction "1_1") (pintype "passive"))
      (node (ref "U5") (pin "100") (pinfunction "VCCIO1_100") (pintype "passive"))
      (node (ref "U5") (pin "116") (pinfunction "VCCIO0_116") (pintype "passive"))
      (node (ref "U5") (pin "126") (pinfunction "VCCEXT_126") (pintype "passive"))
      (node (ref "U5") (pin "136") (pinfunction "VCCIO0_136") (pintype "passive"))
      (node (ref "U5") (pin "19") (pinfunction "VCCEXT_19") (pintype "passive"))
      (node (ref "U5") (pin "46") (pinfunction "VCCIO2_46") (pintype "passive"))
      (node (ref "U5") (pin "56") (pinfunction "VCCEXT_56") (pintype "passive"))
      (node (ref "U5") (pin "64") (pinfunction "VCCIO2_64") (pintype "passive"))
      (node (ref "U5") (pin "82") (pinfunction "VCCIO1_82") (pintype "passive"))
    )
    (net (code "132") (name "GND") (class "Default")
      (node (ref "C35") (pin "2") (pinfunction "2_2") (pintype "passive"))
      (node (ref "C36") (pin "2") (pinfunction "2_2") (pintype "passive"))
      (node (ref "C37") (pin "2") (pinfunction "2_2") (pintype "passive"))
      (node (ref "C38") (pin "2") (pinfunction "2_2") (pintype "passive"))
      (node (ref "C39") (pin "2") (pinfunction "2_2") (pintype "passive"))
      (node (ref "C40") (pin "2") (pinfunction "2_2") (pintype "passive"))
      (node (ref "C41") (pin "2") (pinfunction "2_2") (pintype "passive"))
      (node (ref "C42") (pin "2") (pinfunction "2_2") (pintype "passive"))
      (node (ref "C43") (pin "2") (pinfunction "2_2") (pintype "passive"))
      (node (ref "C44") (pin "1") (pinfunction "1_1") (pintype "passive"))
      (node (ref "P2") (pin "B1") (pinfunction "B1_B1") (pintype "passive"))
      (node (ref "P2") (pin "B10") (pinfunction "B10_B10") (pintype "passive"))
      (node (ref "P2") (pin "B31") (pinfunction "B31_B31") (pintype "passive"))
      (node (ref "P2") (pin "D18") (pinfunction "D18_D18") (pintype "passive"))
      (node (ref "PD2") (pin "6") (pinfunction "GND_6") (pintype "passive"))
      (node (ref "U5") (pin "10") (pinfunction "VSSIO_10") (pintype "passive"))
      (node (ref "U5") (pin "115") (pinfunction "VSSIO_115") (pintype "passive"))
      (node (ref "U5") (pin "135") (pinfunction "VSSIO_135") (pintype "passive"))
      (node (ref "U5") (pin "17") (pinfunction "GND_17") (pintype "passive"))
      (node (ref "U5") (pin "26") (pinfunction "VSSIO_26") (pintype "passive"))
      (node (ref "U5") (pin "47") (pinfunction "VSSIO_47") (pintype "passive"))
      (node (ref "U5") (pin "54") (pinfunction "VSSIO_54") (pintype "passive"))
      (node (ref "U5") (pin "65") (pinfunction "VSSIO_65") (pintype "passive"))
      (node (ref "U5") (pin "83") (pinfunction "VSSIO_83") (pintype "passive"))
      (node (ref "U5") (pin "92") (pinfunction "GND_92") (pintype "passive"))
      (node (ref "U5") (pin "99") (pinfunction "VSSIO_99") (pintype "passive"))
      (node (ref "Y2") (pin "2") (pinfunction "GND_2") (pintype "passive"))
    )
    (net (code "133") (name "Net-(PD2-TCK)") (class "Default")
      (node (ref "PD2") (pin "2") (pinfunction "TCK_2") (pintype "passive"))
      (node (ref "R30") (pin "1") (pinfunction "1_1") (pintype "passive"))
    )
    (net (code "134") (name "Net-(PD2-TDI)") (class "Default")
      (node (ref "PD2") (pin "3") (pinfunction "TDI_3") (pintype "passive"))
      (node (ref "R30") (pin "2") (pinfunction "2_2") (pintype "passive"))
    )
    (net (code "135") (name "Net-(PD2-TDO)") (class "Default")
      (node (ref "PD2") (pin "5") (pinfunction "TDO_5") (pintype "passive"))
      (node (ref "R30") (pin "4") (pinfunction "4_4") (pintype "passive"))
    )
    (net (code "136") (name "Net-(PD2-TMS)") (class "Default")
      (node (ref "PD2") (pin "4") (pinfunction "TMS_4") (pintype "passive"))
      (node (ref "R30") (pin "3") (pinfunction "3_3") (pintype "passive"))
    )
    (net (code "137") (name "Net-(R8-Pad2)") (class "Default")
      (node (ref "R8") (pin "2") (pinfunction "2_2") (pintype "passive"))
      (node (ref "U5") (pin "138") (pinfunction "IO_T_0_138") (pintype "passive"))
    )
    (net (code "138") (name "Net-(R9-Pad1)") (class "Default")
      (node (ref "R9") (pin "1") (pinfunction "1_1") (pintype "passive"))
      (node (ref "U5") (pin "63") (pinfunction "IO_B_2_63") (pintype "passive"))
    )
    (net (code "139") (name "Net-(R9-Pad2)") (class "Default")
      (node (ref "R9") (pin "2") (pinfunction "2_2") (pintype "passive"))
      (node (ref "U5") (pin "67") (pinfunction "IO_B_2_67") (pintype "passive"))
    )
    (net (code "140") (name "Net-(R9-Pad3)") (class "Default")
      (node (ref "R9") (pin "3") (pinfunction "3_3") (pintype "passive"))
      (node (ref "U5") (pin "68") (pinfunction "IO_B_2_68") (pintype "passive"))
    )
    (net (code "141") (name "Net-(R10-Pad2)") (class "Default")
      (node (ref "R10") (pin "2") (pinfunction "2_2") (pintype "passive"))
      (node (ref "U5") (pin "137") (pinfunction "IO_T_0_137") (pintype "passive"))
    )
    (net (code "142") (name "Net-(R11-Pad2)") (class "Default")
      (node (ref "R11") (pin "2") (pinfunction "2_2") (pintype "passive"))
      (node (ref "U5") (pin "134") (pinfunction "IO_T_0_134") (pintype "passive"))
    )
    (net (code "143") (name "Net-(R12-Pad5)") (class "Default")
      (node (ref "R12") (pin "5") (pinfunction "5_5") (pintype "passive"))
      (node (ref "U5") (pin "130") (pinfunction "IO_T_0_130") (pintype "passive"))
    )
    (net (code "144") (name "Net-(R12-Pad6)") (class "Default")
      (node (ref "R12") (pin "6") (pinfunction "6_6") (pintype "passive"))
      (node (ref "U5") (pin "131") (pinfunction "IO_T_0_131") (pintype "passive"))
    )
    (net (code "145") (name "Net-(R12-Pad7)") (class "Default")
      (node (ref "R12") (pin "7") (pinfunction "7_7") (pintype "passive"))
      (node (ref "U5") (pin "132") (pinfunction "IO_T_0_132") (pintype "passive"))
    )
    (net (code "146") (name "Net-(R12-Pad8)") (class "Default")
      (node (ref "R12") (pin "8") (pinfunction "8_8") (pintype "passive"))
      (node (ref "U5") (pin "133") (pinfunction "IO_T_0_133") (pintype "passive"))
    )
    (net (code "147") (name "Net-(R14-Pad5)") (class "Default")
      (node (ref "R14") (pin "5") (pinfunction "5_5") (pintype "passive"))
      (node (ref "U5") (pin "125") (pinfunction "IO_T_0_125") (pintype "passive"))
    )
    (net (code "148") (name "Net-(R14-Pad6)") (class "Default")
      (node (ref "R14") (pin "6") (pinfunction "6_6") (pintype "passive"))
      (node (ref "U5") (pin "127") (pinfunction "IO_T_0_127") (pintype "passive"))
    )
    (net (code "149") (name "Net-(R14-Pad7)") (class "Default")
      (node (ref "R14") (pin "7") (pinfunction "7_7") (pintype "passive"))
      (node (ref "U5") (pin "128") (pinfunction "IO_T_0_128") (pintype "passive"))
    )
    (net (code "150") (name "Net-(R16-Pad5)") (class "Default")
      (node (ref "R16") (pin "5") (pinfunction "5_5") (pintype "passive"))
      (node (ref "U5") (pin "121") (pinfunction "IO_T_0_121") (pintype "passive"))
    )
    (net (code "151") (name "Net-(R16-Pad6)") (class "Default")
      (node (ref "R16") (pin "6") (pinfunction "6_6") (pintype "passive"))
      (node (ref "U5") (pin "122") (pinfunction "IO_T_0_122") (pintype "passive"))
    )
    (net (code "152") (name "Net-(R18-Pad2)") (class "Default")
      (node (ref "R18") (pin "2") (pinfunction "2_2") (pintype "passive"))
      (node (ref "U5") (pin "120") (pinfunction "IO_T_0_120") (pintype "passive"))
    )
    (net (code "153") (name "Net-(R19-Pad2)") (class "Default")
      (node (ref "R19") (pin "2") (pinfunction "2_2") (pintype "passive"))
      (node (ref "U5") (pin "119") (pinfunction "IO_T_0_119") (pintype "passive"))
    )
    (net (code "154") (name "Net-(R21-Pad5)") (class "Default")
      (node (ref "R21") (pin "5") (pinfunction "5_5") (pintype "passive"))
      (node (ref "U5") (pin "113") (pinfunction "IO_T_0_113") (pintype "passive"))
    )
    (net (code "155") (name "Net-(R21-Pad6)") (class "Default")
      (node (ref "R21") (pin "6") (pinfunction "6_6") (pintype "passive"))
      (node (ref "U5") (pin "114") (pinfunction "IO_T_0_114") (pintype "passive"))
    )
    (net (code "156") (name "Net-(R21-Pad7)") (class "Default")
      (node (ref "R21") (pin "7") (pinfunction "7_7") (pintype "passive"))
      (node (ref "U5") (pin "117") (pinfunction "IO_T_0_117") (pintype "passive"))
    )
    (net (code "157") (name "Net-(R21-Pad8)") (class "Default")
      (node (ref "R21") (pin "8") (pinfunction "8_8") (pintype "passive"))
      (node (ref "U5") (pin "118") (pinfunction "IO_T_0_118") (pintype "passive"))
    )
    (net (code "158") (name "Net-(R23-Pad5)") (class "Default")
      (node (ref "R23") (pin "5") (pinfunction "5_5") (pintype "passive"))
      (node (ref "U5") (pin "109") (pinfunction "IO_T_0_109") (pintype "passive"))
    )
    (net (code "159") (name "Net-(R23-Pad6)") (class "Default")
      (node (ref "R23") (pin "6") (pinfunction "6_6") (pintype "passive"))
      (node (ref "U5") (pin "110") (pinfunction "IO_T_0_110") (pintype "passive"))
    )
    (net (code "160") (name "Net-(R23-Pad7)") (class "Default")
      (node (ref "R23") (pin "7") (pinfunction "7_7") (pintype "passive"))
      (node (ref "U5") (pin "111") (pinfunction "IO_T_0_111") (pintype "passive"))
    )
    (net (code "161") (name "Net-(R23-Pad8)") (class "Default")
      (node (ref "R23") (pin "8") (pinfunction "8_8") (pintype "passive"))
      (node (ref "U5") (pin "112") (pinfunction "IO_T_0_112") (pintype "passive"))
    )
    (net (code "162") (name "Net-(R31-Pad1)") (class "Default")
      (node (ref "R31") (pin "1") (pinfunction "1_1") (pintype "passive"))
      (node (ref "U5") (pin "62") (pinfunction "IO_B_2_62") (pintype "passive"))
    )
    (net (code "163") (name "Net-(R31-Pad2)") (class "Default")
      (node (ref "R31") (pin "2") (pinfunction "2_2") (pintype "passive"))
      (node (ref "U5") (pin "61") (pinfunction "IO_B_2_61") (pintype "passive"))
    )
    (net (code "164") (name "Net-(R31-Pad3)") (class "Default")
      (node (ref "R31") (pin "3") (pinfunction "3_3") (pintype "passive"))
      (node (ref "U5") (pin "60") (pinfunction "IO_B_2_60") (pintype "passive"))
    )
    (net (code "165") (name "Net-(R31-Pad4)") (class "Default")
      (node (ref "R31") (pin "4") (pinfunction "4_4") (pintype "passive"))
      (node (ref "U5") (pin "59") (pinfunction "IO_B_2_59") (pintype "passive"))
    )
    (net (code "166") (name "Net-(R32-Pad1)") (class "Default")
      (node (ref "R32") (pin "1") (pinfunction "1_1") (pintype "passive"))
      (node (ref "U5") (pin "58") (pinfunction "IO_B_2_58") (pintype "passive"))
    )
    (net (code "167") (name "Net-(R32-Pad3)") (class "Default")
      (node (ref "R32") (pin "3") (pinfunction "3_3") (pintype "passive"))
      (node (ref "U5") (pin "55") (pinfunction "IO_B_2_55") (pintype "passive"))
    )
    (net (code "168") (name "Net-(R33-Pad1)") (class "Default")
      (node (ref "R33") (pin "1") (pinfunction "1_1") (pintype "passive"))
      (node (ref "U5") (pin "52") (pinfunction "IO_B_2_52") (pintype "passive"))
    )
    (net (code "169") (name "Net-(R33-Pad3)") (class "Default")
      (node (ref "R33") (pin "3") (pinfunction "3_3") (pintype "passive"))
      (node (ref "U5") (pin "50") (pinfunction "IO_B_2_50") (pintype "passive"))
    )
    (net (code "170") (name "Net-(R34-Pad1)") (class "Default")
      (node (ref "R34") (pin "1") (pinfunction "1_1") (pintype "passive"))
      (node (ref "U5") (pin "48") (pinfunction "IO_B_2_48") (pintype "passive"))
    )
    (net (code "171") (name "Net-(R34-Pad2)") (class "Default")
      (node (ref "R34") (pin "2") (pinfunction "2_2") (pintype "passive"))
      (node (ref "U5") (pin "45") (pinfunction "IO_B_2_45") (pintype "passive"))
    )
    (net (code "172") (name "Net-(R34-Pad3)") (class "Default")
      (node (ref "R34") (pin "3") (pinfunction "3_3") (pintype "passive"))
      (node (ref "U5") (pin "44") (pinfunction "IO_B_2_44") (pintype "passive"))
    )
    (net (code "173") (name "Net-(R35-Pad2)") (class "Default")
      (node (ref "R35") (pin "2") (pinfunction "2_2") (pintype "passive"))
      (node (ref "U5") (pin "41") (pinfunction "IO_B_2_41") (pintype "passive"))
    )
    (net (code "174") (name "Net-(R35-Pad3)") (class "Default")
      (node (ref "R35") (pin "3") (pinfunction "3_3") (pintype "passive"))
      (node (ref "U5") (pin "40") (pinfunction "IO_B_2_40") (pintype "passive"))
    )
    (net (code "175") (name "Net-(R35-Pad4)") (class "Default")
      (node (ref "R35") (pin "4") (pinfunction "4_4") (pintype "passive"))
      (node (ref "U5") (pin "39") (pinfunction "IO_B_2_39") (pintype "passive"))
    )
    (net (code "176") (name "Net-(R36-Pad2)") (class "Default")
      (node (ref "R36") (pin "2") (pinfunction "2_2") (pintype "passive"))
      (node (ref "U5") (pin "38") (pinfunction "IO_B_2_38") (pintype "passive"))
    )
    (net (code "177") (name "Net-(R37-Pad2)") (class "Default")
      (node (ref "R37") (pin "2") (pinfunction "2_2") (pintype "passive"))
      (node (ref "U5") (pin "37") (pinfunction "IO_B_2_37") (pintype "passive"))
    )
    (net (code "178") (name "Net-(U5A-IO_B_2,GCLK4)") (class "Default")
      (node (ref "R32") (pin "2") (pinfunction "2_2") (pintype "passive"))
      (node (ref "U5") (pin "57") (pinfunction "IO_B_2,GCLK4_57") (pintype "passive"))
    )
    (net (code "179") (name "Net-(U5A-IO_B_2,GCLKP5)") (class "Default")
      (node (ref "R32") (pin "4") (pinfunction "4_4") (pintype "passive"))
      (node (ref "U5") (pin "53") (pinfunction "IO_B_2,GCLKP5_53") (pintype "passive"))
    )
    (net (code "180") (name "Net-(U5A-IO_B_2,INITN)") (class "Default")
      (node (ref "R9") (pin "4") (pinfunction "4_4") (pintype "passive"))
      (node (ref "U5") (pin "69") (pinfunction "IO_B_2,INITN_69") (pintype "passive"))
    )
    (net (code "181") (name "Net-(U5A-IO_B_2,MISO)") (class "Default")
      (node (ref "R35") (pin "1") (pinfunction "1_1") (pintype "passive"))
      (node (ref "U5") (pin "42") (pinfunction "IO_B_2,MISO_42") (pintype "passive"))
    )
    (net (code "182") (name "Net-(U5A-IO_B_2,MOSI)") (class "Default")
      (node (ref "R33") (pin "2") (pinfunction "2_2") (pintype "passive"))
      (node (ref "U5") (pin "51") (pinfunction "IO_B_2,MOSI_51") (pintype "passive"))
    )
    (net (code "183") (name "Net-(U5A-IO_B_2,SCLK)") (class "Default")
      (node (ref "R33") (pin "4") (pinfunction "4_4") (pintype "passive"))
      (node (ref "U5") (pin "49") (pinfunction "IO_B_2,SCLK_49") (pintype "passive"))
    )
    (net (code "184") (name "Net-(U5A-IO_B_2,SPICSN)") (class "Default")
      (node (ref "R34") (pin "4") (pinfunction "4_4") (pintype "passive"))
      (node (ref "U5") (pin "43") (pinfunction "IO_B_2,SPICSN_43") (pintype "passive"))
    )
    (net (code "185") (name "Net-(U5B-IO_RE0N_1)") (class "Default")
      (node (ref "R13") (pin "3") (pinfunction "3_3") (pintype "passive"))
      (node (ref "U5") (pin "73") (pinfunction "IO_RE0N_1_73") (pintype "passive"))
    )
    (net (code "186") (name "Net-(U5B-IO_RE0P_1)") (class "Default")
      (node (ref "R13") (pin "4") (pinfunction "4_4") (pintype "passive"))
      (node (ref "U5") (pin "74") (pinfunction "IO_RE0P_1_74") (pintype "passive"))
    )
    (net (code "187") (name "Net-(U5B-IO_RE1N_1)") (class "Default")
      (node (ref "R15") (pin "1") (pinfunction "1_1") (pintype "passive"))
      (node (ref "U5") (pin "75") (pinfunction "IO_RE1N_1_75") (pintype "passive"))
    )
    (net (code "188") (name "Net-(U5B-IO_RE1P_1)") (class "Default")
      (node (ref "R15") (pin "2") (pinfunction "2_2") (pintype "passive"))
      (node (ref "U5") (pin "76") (pinfunction "IO_RE1P_1_76") (pintype "passive"))
    )
    (net (code "189") (name "Net-(U5B-IO_RE2N_1)") (class "Default")
      (node (ref "R15") (pin "3") (pinfunction "3_3") (pintype "passive"))
      (node (ref "U5") (pin "77") (pinfunction "IO_RE2N_1_77") (pintype "passive"))
    )
    (net (code "190") (name "Net-(U5B-IO_RE2P_1)") (class "Default")
      (node (ref "R15") (pin "4") (pinfunction "4_4") (pintype "passive"))
      (node (ref "U5") (pin "78") (pinfunction "IO_RE2P_1_78") (pintype "passive"))
    )
    (net (code "191") (name "Net-(U5B-IO_RE3N_1)") (class "Default")
      (node (ref "R17") (pin "1") (pinfunction "1_1") (pintype "passive"))
      (node (ref "U5") (pin "79") (pinfunction "IO_RE3N_1_79") (pintype "passive"))
    )
    (net (code "192") (name "Net-(U5B-IO_RE3P_1)") (class "Default")
      (node (ref "R17") (pin "2") (pinfunction "2_2") (pintype "passive"))
      (node (ref "U5") (pin "80") (pinfunction "IO_RE3P_1_80") (pintype "passive"))
    )
    (net (code "193") (name "Net-(U5B-IO_RE4N_1)") (class "Default")
      (node (ref "R17") (pin "3") (pinfunction "3_3") (pintype "passive"))
      (node (ref "U5") (pin "81") (pinfunction "IO_RE4N_1_81") (pintype "passive"))
    )
    (net (code "194") (name "Net-(U5B-IO_RE4P_1)") (class "Default")
      (node (ref "R17") (pin "4") (pinfunction "4_4") (pintype "passive"))
      (node (ref "U5") (pin "84") (pinfunction "IO_RE4P_1_84") (pintype "passive"))
    )
    (net (code "195") (name "Net-(U5B-IO_RE5N_1)") (class "Default")
      (node (ref "R20") (pin "1") (pinfunction "1_1") (pintype "passive"))
      (node (ref "U5") (pin "85") (pinfunction "IO_RE5N_1_85") (pintype "passive"))
    )
    (net (code "196") (name "Net-(U5B-IO_RE5P_1)") (class "Default")
      (node (ref "R20") (pin "2") (pinfunction "2_2") (pintype "passive"))
      (node (ref "U5") (pin "86") (pinfunction "IO_RE5P_1_86") (pintype "passive"))
    )
    (net (code "197") (name "Net-(U5B-IO_RE6N_1)") (class "Default")
      (node (ref "R20") (pin "3") (pinfunction "3_3") (pintype "passive"))
      (node (ref "U5") (pin "87") (pinfunction "IO_RE6N_1_87") (pintype "passive"))
    )
    (net (code "198") (name "Net-(U5B-IO_RE6P_1)") (class "Default")
      (node (ref "R20") (pin "4") (pinfunction "4_4") (pintype "passive"))
      (node (ref "U5") (pin "88") (pinfunction "IO_RE6P_1_88") (pintype "passive"))
    )
    (net (code "199") (name "Net-(U5B-IO_RE7N_1,GCLK2)") (class "Default")
      (node (ref "R22") (pin "1") (pinfunction "1_1") (pintype "passive"))
      (node (ref "U5") (pin "89") (pinfunction "IO_RE7N_1,GCLK2_89") (pintype "passive"))
    )
    (net (code "200") (name "Net-(U5B-IO_RE7P_1,GCLK3)") (class "Default")
      (node (ref "R22") (pin "2") (pinfunction "2_2") (pintype "passive"))
      (node (ref "U5") (pin "91") (pinfunction "IO_RE7P_1,GCLK3_91") (pintype "passive"))
    )
    (net (code "201") (name "Net-(U5B-IO_RE8N_1)") (class "Default")
      (node (ref "R22") (pin "3") (pinfunction "3_3") (pintype "passive"))
      (node (ref "U5") (pin "93") (pinfunction "IO_RE8N_1_93") (pintype "passive"))
    )
    (net (code "202") (name "Net-(U5B-IO_RE8P_1)") (class "Default")
      (node (ref "R22") (pin "4") (pinfunction "4_4") (pintype "passive"))
      (node (ref "U5") (pin "94") (pinfunction "IO_RE8P_1_94") (pintype "passive"))
    )
    (net (code "203") (name "Net-(U5B-IO_RE9N_1)") (class "Default")
      (node (ref "R24") (pin "1") (pinfunction "1_1") (pintype "passive"))
      (node (ref "U5") (pin "95") (pinfunction "IO_RE9N_1_95") (pintype "passive"))
    )
    (net (code "204") (name "Net-(U5B-IO_RE9P_1)") (class "Default")
      (node (ref "R24") (pin "2") (pinfunction "2_2") (pintype "passive"))
      (node (ref "U5") (pin "96") (pinfunction "IO_RE9P_1_96") (pintype "passive"))
    )
    (net (code "205") (name "Net-(U5B-IO_RE10N_1)") (class "Default")
      (node (ref "R24") (pin "3") (pinfunction "3_3") (pintype "passive"))
      (node (ref "U5") (pin "97") (pinfunction "IO_RE10N_1_97") (pintype "passive"))
    )
    (net (code "206") (name "Net-(U5B-IO_RE10P_1)") (class "Default")
      (node (ref "R24") (pin "4") (pinfunction "4_4") (pintype "passive"))
      (node (ref "U5") (pin "98") (pinfunction "IO_RE10P_1_98") (pintype "passive"))
    )
    (net (code "207") (name "Net-(U5B-IO_RE11N_1)") (class "Default")
      (node (ref "R29") (pin "1") (pinfunction "1_1") (pintype "passive"))
      (node (ref "U5") (pin "101") (pinfunction "IO_RE11N_1_101") (pintype "passive"))
    )
    (net (code "208") (name "Net-(U5B-IO_RE11P_1)") (class "Default")
      (node (ref "R29") (pin "2") (pinfunction "2_2") (pintype "passive"))
      (node (ref "U5") (pin "102") (pinfunction "IO_RE11P_1_102") (pintype "passive"))
    )
    (net (code "209") (name "Net-(U5B-IO_RE12N_1)") (class "Default")
      (node (ref "R29") (pin "3") (pinfunction "3_3") (pintype "passive"))
      (node (ref "U5") (pin "103") (pinfunction "IO_RE12N_1_103") (pintype "passive"))
    )
    (net (code "210") (name "Net-(U5B-IO_RE12P_1)") (class "Default")
      (node (ref "R29") (pin "4") (pinfunction "4_4") (pintype "passive"))
      (node (ref "U5") (pin "104") (pinfunction "IO_RE12P_1_104") (pintype "passive"))
    )
    (net (code "211") (name "Net-(U5B-IO_RE13N_1)") (class "Default")
      (node (ref "R25") (pin "5") (pinfunction "5_5") (pintype "passive"))
      (node (ref "U5") (pin "105") (pinfunction "IO_RE13N_1_105") (pintype "passive"))
    )
    (net (code "212") (name "Net-(U5B-IO_RE13P_1)") (class "Default")
      (node (ref "R25") (pin "6") (pinfunction "6_6") (pintype "passive"))
      (node (ref "U5") (pin "106") (pinfunction "IO_RE13P_1_106") (pintype "passive"))
    )
    (net (code "213") (name "Net-(U5B-IO_RE14N_1)") (class "Default")
      (node (ref "R25") (pin "7") (pinfunction "7_7") (pintype "passive"))
      (node (ref "U5") (pin "107") (pinfunction "IO_RE14N_1_107") (pintype "passive"))
    )
    (net (code "214") (name "Net-(U5B-IO_RE14P_1)") (class "Default")
      (node (ref "R25") (pin "8") (pinfunction "8_8") (pintype "passive"))
      (node (ref "U5") (pin "108") (pinfunction "IO_RE14P_1_108") (pintype "passive"))
    )
    (net (code "215") (name "Net-(U5B-IO_T_0,GCLK0)") (class "Default")
      (node (ref "R16") (pin "8") (pinfunction "8_8") (pintype "passive"))
      (node (ref "U5") (pin "124") (pinfunction "IO_T_0,GCLK0_124") (pintype "passive"))
    )
    (net (code "216") (name "Net-(U5B-IO_T_0,GCLK1)") (class "Default")
      (node (ref "R16") (pin "7") (pinfunction "7_7") (pintype "passive"))
      (node (ref "U5") (pin "123") (pinfunction "IO_T_0,GCLK1_123") (pintype "passive"))
    )
    (net (code "217") (name "Net-(U5B-IO_T_0,_JTAGEN)") (class "Default")
      (node (ref "R14") (pin "8") (pinfunction "8_8") (pintype "passive"))
      (node (ref "U5") (pin "129") (pinfunction "IO_T_0,_JTAGEN_129") (pintype "passive"))
    )
    (net (code "218") (name "unconnected-(P2-PadD16)") (class "Default")
      (node (ref "P2") (pin "D16") (pinfunction "D16_D16") (pintype "passive"))
    )
    (net (code "219") (name "unconnected-(U5B-IO_T_0-Pad140)") (class "Default")
      (node (ref "U5") (pin "140") (pinfunction "IO_T_0_140") (pintype "passive"))
    )
    (net (code "220") (name "unconnected-(U5B-IO_T_0-Pad141)") (class "Default")
      (node (ref "U5") (pin "141") (pinfunction "IO_T_0_141") (pintype "passive"))
    )
    (net (code "221") (name "unconnected-(U5B-IO_T_0-Pad142)") (class "Default")
      (node (ref "U5") (pin "142") (pinfunction "IO_T_0_142") (pintype "passive"))
    )
    (net (code "222") (name "unconnected-(U5B-IO_T_0-Pad143)") (class "Default")
      (node (ref "U5") (pin "143") (pinfunction "IO_T_0_143") (pintype "passive"))
    )
    (net (code "223") (name "unconnected-(U5B-IO_T_0-Pad144)") (class "Default")
      (node (ref "U5") (pin "144") (pinfunction "IO_T_0_144") (pintype "passive"))
    )
    (net (code "224") (name "unconnected-(U5C-NC-Pad90)") (class "Default")
      (node (ref "U5") (pin "90") (pinfunction "NC_90") (pintype "passive"))
    )
    (net (code "225") (name "unconnected-(Y2-NC-Pad1)") (class "Default")
      (node (ref "Y2") (pin "1") (pinfunction "NC_1") (pintype "passive+no_connect"))
    )
  )
)
